# SCH_gas-monitor.net
KiCad netlist of a schematic drawn in EasyEDA
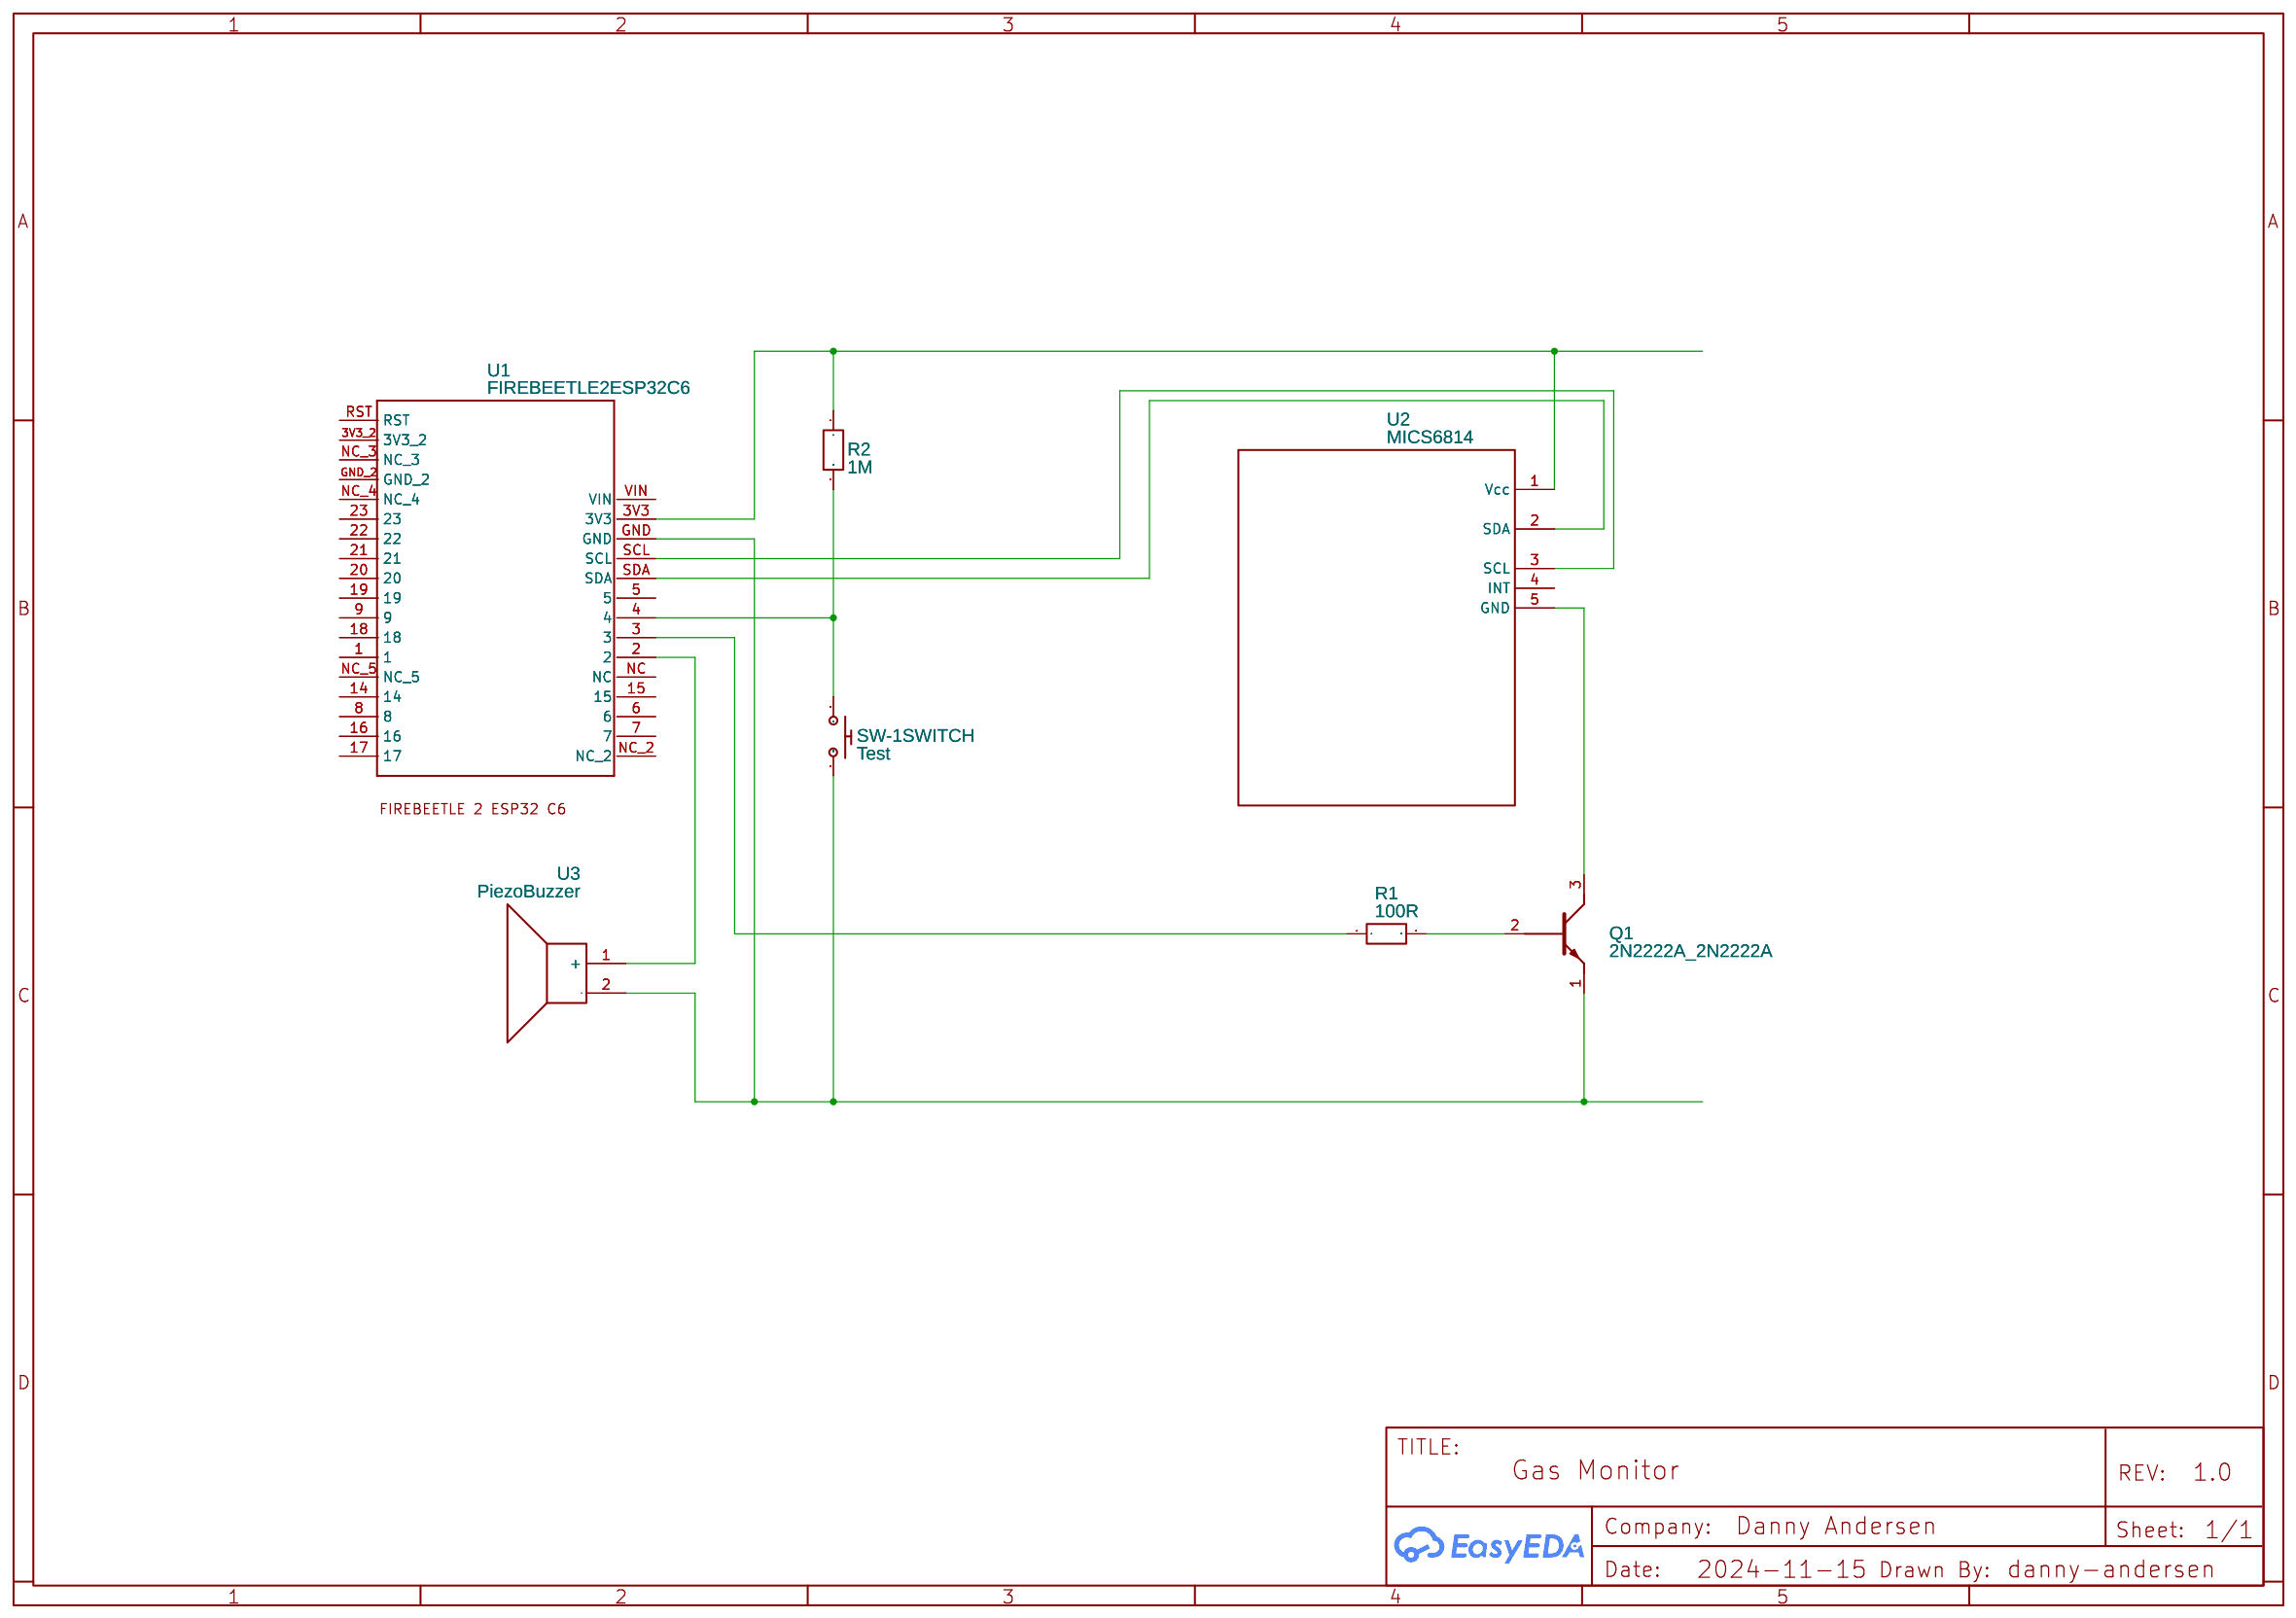
[diagram p0: schematic sheet]

(export (version "E")
  (design (tool "Eeschema 10.0.6"))
  (components
    (comp (ref "Q1") (value "2N2222A_2N2222A") (libsource (lib "") (part "2N2222A_2N2222A")))
    (comp (ref "R1") (value "100R") (libsource (lib "") (part "R_0603_EU_1")))
    (comp (ref "R2") (value "1M") (libsource (lib "") (part "R_0603_EU")))
    (comp (ref "SW-1SWITCH") (value "Test") (libsource (lib "") (part "Push Button")))
    (comp (ref "U1") (value "FIREBEETLE2ESP32C6") (libsource (lib "") (part "FIREBEETLE2ESP32C6")))
    (comp (ref "U2") (value "MICS6814") (libsource (lib "") (part "mics6814")))
    (comp (ref "U3") (value "PiezoBuzzer") (libsource (lib "") (part "PiezoBuzzer")))
  )
  (nets
    (net (code "1") (name "Net-(Q1-Pad2)") (class "Default")
      (node (ref "Q1") (pin "2") (pintype "unspecified"))
      (node (ref "R1") (pin "2") (pinfunction "2_2") (pintype "unspecified"))
    )
    (net (code "2") (name "Net-(R1-Pad1)") (class "Default")
      (node (ref "R1") (pin "1") (pinfunction "1_1") (pintype "unspecified"))
      (node (ref "U1") (pin "3") (pinfunction "3_3") (pintype "bidirectional"))
    )
    (net (code "3") (name "Net-(SW-1SWITCH-P$1)") (class "Default")
      (node (ref "R2") (pin "2") (pinfunction "2_2") (pintype "unspecified"))
      (node (ref "SW-1SWITCH") (pin "1") (pinfunction "P$1_1") (pintype "unspecified"))
      (node (ref "U1") (pin "4") (pinfunction "4_4") (pintype "bidirectional"))
    )
    (net (code "4") (name "Net-(SW-1SWITCH-P$2)") (class "Default")
      (node (ref "Q1") (pin "1") (pintype "unspecified"))
      (node (ref "SW-1SWITCH") (pin "2") (pinfunction "P$2_2") (pintype "unspecified"))
      (node (ref "U1") (pin "GND") (pinfunction "GND_GND") (pintype "bidirectional"))
      (node (ref "U3") (pin "2") (pinfunction "-_2") (pintype "unspecified"))
    )
    (net (code "5") (name "Net-(U2-GND)") (class "Default")
      (node (ref "Q1") (pin "3") (pintype "unspecified"))
      (node (ref "U2") (pin "5") (pinfunction "GND_5") (pintype "unspecified"))
    )
    (net (code "6") (name "Net-(U2-SCL)") (class "Default")
      (node (ref "U1") (pin "SCL") (pinfunction "SCL_SCL") (pintype "bidirectional"))
      (node (ref "U2") (pin "3") (pinfunction "SCL_3") (pintype "unspecified"))
    )
    (net (code "7") (name "Net-(U2-SDA)") (class "Default")
      (node (ref "U1") (pin "SDA") (pinfunction "SDA_SDA") (pintype "bidirectional"))
      (node (ref "U2") (pin "2") (pinfunction "SDA_2") (pintype "unspecified"))
    )
    (net (code "8") (name "Net-(U2-Vcc)") (class "Default")
      (node (ref "R2") (pin "1") (pinfunction "1_1") (pintype "unspecified"))
      (node (ref "U1") (pin "3V3") (pinfunction "3V3_3V3") (pintype "bidirectional"))
      (node (ref "U2") (pin "1") (pinfunction "Vcc_1") (pintype "unspecified"))
    )
    (net (code "9") (name "Net-(U3-+)") (class "Default")
      (node (ref "U1") (pin "2") (pinfunction "2_2") (pintype "bidirectional"))
      (node (ref "U3") (pin "1") (pinfunction "+_1") (pintype "unspecified"))
    )
    (net (code "10") (name "unconnected-(U1-Pad1)") (class "Default")
      (node (ref "U1") (pin "1") (pinfunction "1_1") (pintype "bidirectional"))
    )
    (net (code "11") (name "unconnected-(U1-Pad3V3_2)") (class "Default")
      (node (ref "U1") (pin "3V3_2") (pinfunction "3V3_2_3V3_2") (pintype "bidirectional"))
    )
    (net (code "12") (name "unconnected-(U1-Pad5)") (class "Default")
      (node (ref "U1") (pin "5") (pinfunction "5_5") (pintype "bidirectional"))
    )
    (net (code "13") (name "unconnected-(U1-Pad6)") (class "Default")
      (node (ref "U1") (pin "6") (pinfunction "6_6") (pintype "bidirectional"))
    )
    (net (code "14") (name "unconnected-(U1-Pad7)") (class "Default")
      (node (ref "U1") (pin "7") (pinfunction "7_7") (pintype "bidirectional"))
    )
    (net (code "15") (name "unconnected-(U1-Pad8)") (class "Default")
      (node (ref "U1") (pin "8") (pinfunction "8_8") (pintype "bidirectional"))
    )
    (net (code "16") (name "unconnected-(U1-Pad9)") (class "Default")
      (node (ref "U1") (pin "9") (pinfunction "9_9") (pintype "bidirectional"))
    )
    (net (code "17") (name "unconnected-(U1-Pad14)") (class "Default")
      (node (ref "U1") (pin "14") (pinfunction "14_14") (pintype "bidirectional"))
    )
    (net (code "18") (name "unconnected-(U1-Pad15)") (class "Default")
      (node (ref "U1") (pin "15") (pinfunction "15_15") (pintype "bidirectional"))
    )
    (net (code "19") (name "unconnected-(U1-Pad16)") (class "Default")
      (node (ref "U1") (pin "16") (pinfunction "16_16") (pintype "bidirectional"))
    )
    (net (code "20") (name "unconnected-(U1-Pad17)") (class "Default")
      (node (ref "U1") (pin "17") (pinfunction "17_17") (pintype "bidirectional"))
    )
    (net (code "21") (name "unconnected-(U1-Pad18)") (class "Default")
      (node (ref "U1") (pin "18") (pinfunction "18_18") (pintype "bidirectional"))
    )
    (net (code "22") (name "unconnected-(U1-Pad19)") (class "Default")
      (node (ref "U1") (pin "19") (pinfunction "19_19") (pintype "bidirectional"))
    )
    (net (code "23") (name "unconnected-(U1-Pad20)") (class "Default")
      (node (ref "U1") (pin "20") (pinfunction "20_20") (pintype "bidirectional"))
    )
    (net (code "24") (name "unconnected-(U1-Pad21)") (class "Default")
      (node (ref "U1") (pin "21") (pinfunction "21_21") (pintype "bidirectional"))
    )
    (net (code "25") (name "unconnected-(U1-Pad22)") (class "Default")
      (node (ref "U1") (pin "22") (pinfunction "22_22") (pintype "bidirectional"))
    )
    (net (code "26") (name "unconnected-(U1-Pad23)") (class "Default")
      (node (ref "U1") (pin "23") (pinfunction "23_23") (pintype "bidirectional"))
    )
    (net (code "27") (name "unconnected-(U1-PadGND_2)") (class "Default")
      (node (ref "U1") (pin "GND_2") (pinfunction "GND_2_GND_2") (pintype "bidirectional"))
    )
    (net (code "28") (name "unconnected-(U1-PadNC)") (class "Default")
      (node (ref "U1") (pin "NC") (pinfunction "NC_NC") (pintype "bidirectional"))
    )
    (net (code "29") (name "unconnected-(U1-PadNC_2)") (class "Default")
      (node (ref "U1") (pin "NC_2") (pinfunction "NC_2_NC_2") (pintype "bidirectional"))
    )
    (net (code "30") (name "unconnected-(U1-PadNC_3)") (class "Default")
      (node (ref "U1") (pin "NC_3") (pinfunction "NC_3_NC_3") (pintype "bidirectional"))
    )
    (net (code "31") (name "unconnected-(U1-PadNC_4)") (class "Default")
      (node (ref "U1") (pin "NC_4") (pinfunction "NC_4_NC_4") (pintype "bidirectional"))
    )
    (net (code "32") (name "unconnected-(U1-PadNC_5)") (class "Default")
      (node (ref "U1") (pin "NC_5") (pinfunction "NC_5_NC_5") (pintype "bidirectional"))
    )
    (net (code "33") (name "unconnected-(U1-PadRST)") (class "Default")
      (node (ref "U1") (pin "RST") (pinfunction "RST_RST") (pintype "bidirectional"))
    )
    (net (code "34") (name "unconnected-(U1-PadVIN)") (class "Default")
      (node (ref "U1") (pin "VIN") (pinfunction "VIN_VIN") (pintype "bidirectional"))
    )
    (net (code "35") (name "unconnected-(U2-INT-Pad4)") (class "Default")
      (node (ref "U2") (pin "4") (pinfunction "INT_4") (pintype "unspecified"))
    )
  )
)
